# Sensor_Python.net
KiCad netlist of a schematic drawn in EAGLE
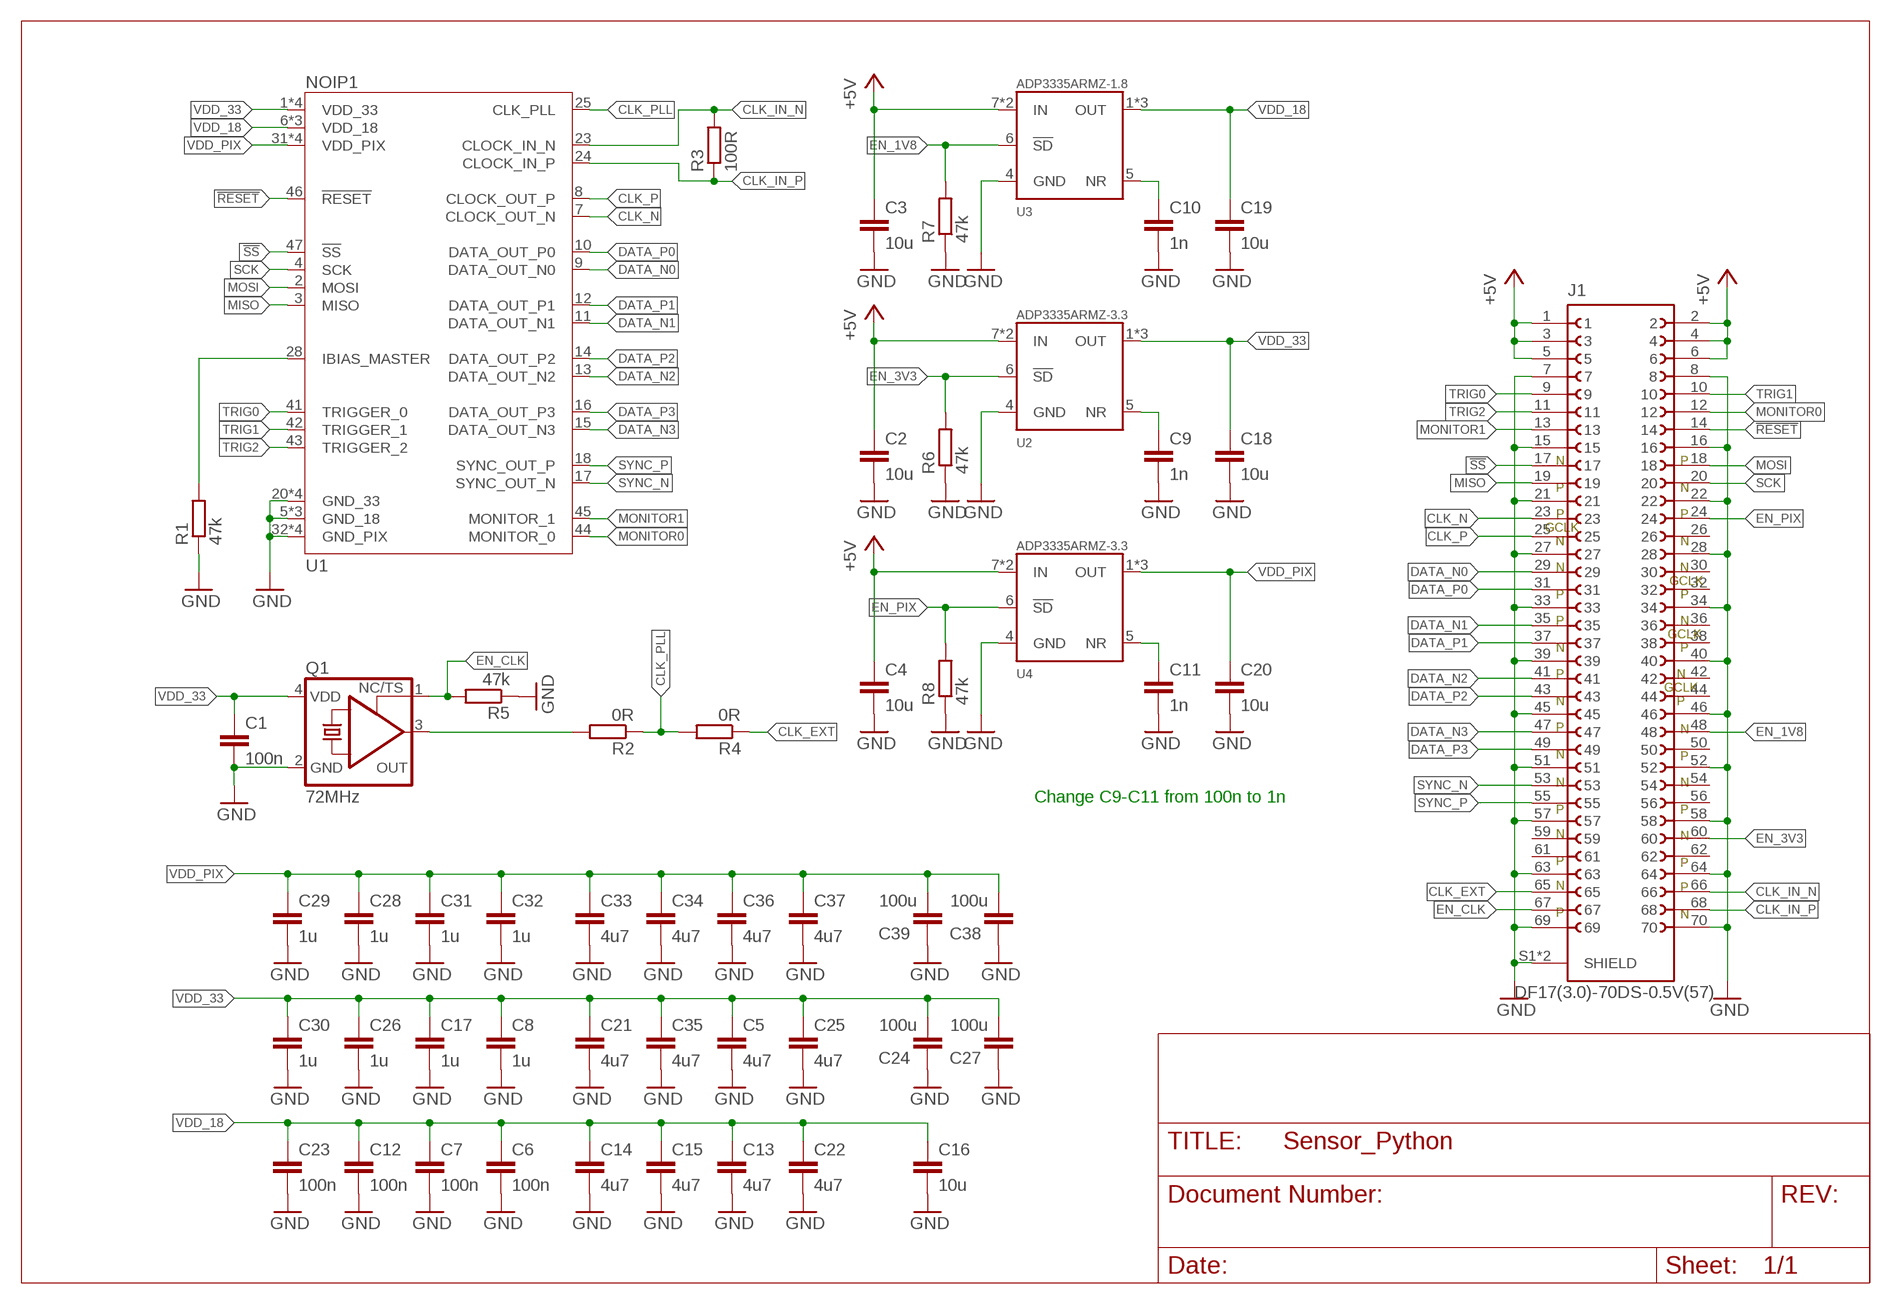
[diagram p0: schematic, sheet 1]

(export (version "E")
  (design (tool "Eeschema 10.0.6"))
  (components
    (comp (ref "C1")
      (value "100n")
      (footprint "eagle-import:C0402")
      (libsource (lib "eagle-import") (part "C-EUC0402"))
    )
    (comp (ref "C2")
      (value "10u")
      (footprint "eagle-import:C0603")
      (libsource (lib "eagle-import") (part "rcl_334_C-EUC0603"))
    )
    (comp (ref "C3")
      (value "10u")
      (footprint "eagle-import:C0603")
      (libsource (lib "eagle-import") (part "rcl_334_C-EUC0603"))
    )
    (comp (ref "C4")
      (value "10u")
      (footprint "eagle-import:C0603")
      (libsource (lib "eagle-import") (part "rcl_334_C-EUC0603"))
    )
    (comp (ref "C5")
      (value "4u7")
      (footprint "eagle-import:C0603")
      (libsource (lib "eagle-import") (part "rcl_334_C-EUC0603"))
    )
    (comp (ref "C6")
      (value "100n")
      (footprint "eagle-import:C0402")
      (libsource (lib "eagle-import") (part "rcl_334_C-EUC0402"))
    )
    (comp (ref "C7")
      (value "100n")
      (footprint "eagle-import:C0402")
      (libsource (lib "eagle-import") (part "rcl_334_C-EUC0402"))
    )
    (comp (ref "C8")
      (value "1u")
      (footprint "eagle-import:C0402")
      (libsource (lib "eagle-import") (part "rcl_334_C-EUC0402"))
    )
    (comp (ref "C9")
      (value "1n")
      (footprint "eagle-import:C0402")
      (libsource (lib "eagle-import") (part "rcl_334_C-EUC0402"))
    )
    (comp (ref "C10")
      (value "1n")
      (footprint "eagle-import:C0402")
      (libsource (lib "eagle-import") (part "rcl_334_C-EUC0402"))
    )
    (comp (ref "C11")
      (value "1n")
      (footprint "eagle-import:C0402")
      (libsource (lib "eagle-import") (part "rcl_334_C-EUC0402"))
    )
    (comp (ref "C12")
      (value "100n")
      (footprint "eagle-import:C0402")
      (libsource (lib "eagle-import") (part "rcl_334_C-EUC0402"))
    )
    (comp (ref "C13")
      (value "4u7")
      (footprint "eagle-import:C0603")
      (libsource (lib "eagle-import") (part "rcl_334_C-EUC0603"))
    )
    (comp (ref "C14")
      (value "4u7")
      (footprint "eagle-import:C0603")
      (libsource (lib "eagle-import") (part "rcl_334_C-EUC0603"))
    )
    (comp (ref "C15")
      (value "4u7")
      (footprint "eagle-import:C0603")
      (libsource (lib "eagle-import") (part "rcl_334_C-EUC0603"))
    )
    (comp (ref "C16")
      (value "10u")
      (footprint "eagle-import:C0603")
      (libsource (lib "eagle-import") (part "rcl_334_C-EUC0603"))
    )
    (comp (ref "C17")
      (value "1u")
      (footprint "eagle-import:C0402")
      (libsource (lib "eagle-import") (part "rcl_334_C-EUC0402"))
    )
    (comp (ref "C18")
      (value "10u")
      (footprint "eagle-import:C0603")
      (libsource (lib "eagle-import") (part "rcl_334_C-EUC0603"))
    )
    (comp (ref "C19")
      (value "10u")
      (footprint "eagle-import:C0603")
      (libsource (lib "eagle-import") (part "rcl_334_C-EUC0603"))
    )
    (comp (ref "C20")
      (value "10u")
      (footprint "eagle-import:C0603")
      (libsource (lib "eagle-import") (part "rcl_334_C-EUC0603"))
    )
    (comp (ref "C21")
      (value "4u7")
      (footprint "eagle-import:C0603")
      (libsource (lib "eagle-import") (part "rcl_334_C-EUC0603"))
    )
    (comp (ref "C22")
      (value "4u7")
      (footprint "eagle-import:C0603")
      (libsource (lib "eagle-import") (part "rcl_334_C-EUC0603"))
    )
    (comp (ref "C23")
      (value "100n")
      (footprint "eagle-import:C0402")
      (libsource (lib "eagle-import") (part "rcl_334_C-EUC0402"))
    )
    (comp (ref "C24")
      (value "100u")
      (footprint "eagle-import:C1206")
      (libsource (lib "eagle-import") (part "rcl_334_C-EUC1206"))
    )
    (comp (ref "C25")
      (value "4u7")
      (footprint "eagle-import:C0603")
      (libsource (lib "eagle-import") (part "rcl_334_C-EUC0603"))
    )
    (comp (ref "C26")
      (value "1u")
      (footprint "eagle-import:C0402")
      (libsource (lib "eagle-import") (part "rcl_334_C-EUC0402"))
    )
    (comp (ref "C27")
      (value "100u")
      (footprint "eagle-import:C1206")
      (libsource (lib "eagle-import") (part "rcl_334_C-EUC1206"))
    )
    (comp (ref "C28")
      (value "1u")
      (footprint "eagle-import:C0402")
      (libsource (lib "eagle-import") (part "rcl_334_C-EUC0402"))
    )
    (comp (ref "C29")
      (value "1u")
      (footprint "eagle-import:C0402")
      (libsource (lib "eagle-import") (part "rcl_334_C-EUC0402"))
    )
    (comp (ref "C30")
      (value "1u")
      (footprint "eagle-import:C0402")
      (libsource (lib "eagle-import") (part "rcl_334_C-EUC0402"))
    )
    (comp (ref "C31")
      (value "1u")
      (footprint "eagle-import:C0402")
      (libsource (lib "eagle-import") (part "rcl_334_C-EUC0402"))
    )
    (comp (ref "C32")
      (value "1u")
      (footprint "eagle-import:C0402")
      (libsource (lib "eagle-import") (part "rcl_334_C-EUC0402"))
    )
    (comp (ref "C33")
      (value "4u7")
      (footprint "eagle-import:C0603")
      (libsource (lib "eagle-import") (part "rcl_334_C-EUC0603"))
    )
    (comp (ref "C34")
      (value "4u7")
      (footprint "eagle-import:C0603")
      (libsource (lib "eagle-import") (part "rcl_334_C-EUC0603"))
    )
    (comp (ref "C35")
      (value "4u7")
      (footprint "eagle-import:C0603")
      (libsource (lib "eagle-import") (part "rcl_334_C-EUC0603"))
    )
    (comp (ref "C36")
      (value "4u7")
      (footprint "eagle-import:C0603")
      (libsource (lib "eagle-import") (part "rcl_334_C-EUC0603"))
    )
    (comp (ref "C37")
      (value "4u7")
      (footprint "eagle-import:C0603")
      (libsource (lib "eagle-import") (part "rcl_334_C-EUC0603"))
    )
    (comp (ref "C38")
      (value "100u")
      (footprint "eagle-import:C1206")
      (libsource (lib "eagle-import") (part "rcl_334_C-EUC1206"))
    )
    (comp (ref "C39")
      (value "100u")
      (footprint "eagle-import:C1206")
      (libsource (lib "eagle-import") (part "rcl_334_C-EUC1206"))
    )
    (comp (ref "J1")
      (value "DF17(3.0)-70DS-0.5V(57)")
      (footprint "eagle-import:DF17(3.0)-70DS-0.5V(57)")
      (libsource (lib "eagle-import") (part "DF17(3.0)-70DS-0.5V(57)"))
    )
    (comp (ref "Q1")
      (value "72MHz")
      (footprint "eagle-import:3.2X2.5_KXO-V96")
      (libsource (lib "eagle-import") (part "KXO-PXO/XO-V96"))
    )
    (comp (ref "R1")
      (value "47k")
      (footprint "eagle-import:R0402")
      (libsource (lib "eagle-import") (part "R-EU_R0402"))
    )
    (comp (ref "R2")
      (value "0R")
      (footprint "eagle-import:R0402")
      (libsource (lib "eagle-import") (part "R-EU_R0402"))
    )
    (comp (ref "R3")
      (value "100R")
      (footprint "eagle-import:R0402")
      (libsource (lib "eagle-import") (part "R-EU_R0402"))
    )
    (comp (ref "R4")
      (value "0R")
      (footprint "eagle-import:R0402")
      (libsource (lib "eagle-import") (part "R-EU_R0402"))
    )
    (comp (ref "R5")
      (value "47k")
      (footprint "eagle-import:R0402")
      (libsource (lib "eagle-import") (part "R-EU_R0402"))
    )
    (comp (ref "R6")
      (value "47k")
      (footprint "eagle-import:R0402")
      (libsource (lib "eagle-import") (part "R-EU_R0402"))
    )
    (comp (ref "R7")
      (value "47k")
      (footprint "eagle-import:R0402")
      (libsource (lib "eagle-import") (part "R-EU_R0402"))
    )
    (comp (ref "R8")
      (value "47k")
      (footprint "eagle-import:R0402")
      (libsource (lib "eagle-import") (part "R-EU_R0402"))
    )
    (comp (ref "U1")
      (value "NOIP1")
      (footprint "eagle-import:LCC-44")
      (libsource (lib "eagle-import") (part "NOIP1"))
    )
    (comp (ref "U2")
      (value "ADP3335ARMZ-3.3")
      (footprint "eagle-import:MSOP08")
      (libsource (lib "eagle-import") (part "ADP3335ARMZ"))
    )
    (comp (ref "U3")
      (value "ADP3335ARMZ-1.8")
      (footprint "eagle-import:MSOP08")
      (libsource (lib "eagle-import") (part "ADP3335ARMZ"))
    )
    (comp (ref "U4")
      (value "ADP3335ARMZ-3.3")
      (footprint "eagle-import:MSOP08")
      (libsource (lib "eagle-import") (part "ADP3335ARMZ"))
    )
  )
  (nets
    (net (code "1") (name "+5V") (class "Default")
      (node (ref "C2") (pin "1") (pinfunction "1_1") (pintype "passive"))
      (node (ref "C3") (pin "1") (pinfunction "1_1") (pintype "passive"))
      (node (ref "C4") (pin "1") (pinfunction "1_1") (pintype "passive"))
      (node (ref "J1") (pin "1") (pinfunction "1_1") (pintype "passive"))
      (node (ref "J1") (pin "2") (pinfunction "2_2") (pintype "passive"))
      (node (ref "J1") (pin "3") (pinfunction "3_3") (pintype "passive"))
      (node (ref "J1") (pin "4") (pinfunction "4_4") (pintype "passive"))
      (node (ref "J1") (pin "5") (pinfunction "5_5") (pintype "passive"))
      (node (ref "J1") (pin "6") (pinfunction "6_6") (pintype "passive"))
      (node (ref "U2") (pin "7") (pinfunction "IN_7") (pintype "power_in"))
      (node (ref "U2") (pin "8") (pinfunction "IN_8") (pintype "power_in"))
      (node (ref "U3") (pin "7") (pinfunction "IN_7") (pintype "power_in"))
      (node (ref "U3") (pin "8") (pinfunction "IN_8") (pintype "power_in"))
      (node (ref "U4") (pin "7") (pinfunction "IN_7") (pintype "power_in"))
      (node (ref "U4") (pin "8") (pinfunction "IN_8") (pintype "power_in"))
    )
    (net (code "2") (name "/~{RESET}") (class "Default")
      (node (ref "J1") (pin "14") (pinfunction "14_14") (pintype "passive"))
      (node (ref "U1") (pin "46") (pinfunction "~{RESET}_46") (pintype "input"))
    )
    (net (code "3") (name "/~{SS}") (class "Default")
      (node (ref "J1") (pin "17") (pinfunction "17_17") (pintype "passive"))
      (node (ref "U1") (pin "47") (pinfunction "~{SS}_47") (pintype "input"))
    )
    (net (code "4") (name "CLK_EXT") (class "Default")
      (node (ref "J1") (pin "65") (pinfunction "65_65") (pintype "passive"))
      (node (ref "R4") (pin "1") (pinfunction "1_1") (pintype "passive"))
    )
    (net (code "5") (name "CLK_IN_N") (class "Default")
      (node (ref "J1") (pin "66") (pinfunction "66_66") (pintype "passive"))
      (node (ref "R3") (pin "2") (pinfunction "2_2") (pintype "passive"))
      (node (ref "U1") (pin "23") (pinfunction "CLOCK_IN_N_23") (pintype "input"))
    )
    (net (code "6") (name "CLK_IN_P") (class "Default")
      (node (ref "J1") (pin "68") (pinfunction "68_68") (pintype "passive"))
      (node (ref "R3") (pin "1") (pinfunction "1_1") (pintype "passive"))
      (node (ref "U1") (pin "24") (pinfunction "CLOCK_IN_P_24") (pintype "input"))
    )
    (net (code "7") (name "CLK_N") (class "Default")
      (node (ref "J1") (pin "23") (pinfunction "23_23") (pintype "passive"))
      (node (ref "U1") (pin "7") (pinfunction "CLOCK_OUT_N_7") (pintype "output"))
    )
    (net (code "8") (name "CLK_P") (class "Default")
      (node (ref "J1") (pin "25") (pinfunction "25_25") (pintype "passive"))
      (node (ref "U1") (pin "8") (pinfunction "CLOCK_OUT_P_8") (pintype "output"))
    )
    (net (code "9") (name "CLK_PLL") (class "Default")
      (node (ref "R2") (pin "1") (pinfunction "1_1") (pintype "passive"))
      (node (ref "R4") (pin "2") (pinfunction "2_2") (pintype "passive"))
      (node (ref "U1") (pin "25") (pinfunction "CLK_PLL_25") (pintype "input"))
    )
    (net (code "10") (name "DATA_N0") (class "Default")
      (node (ref "J1") (pin "29") (pinfunction "29_29") (pintype "passive"))
      (node (ref "U1") (pin "9") (pinfunction "DATA_OUT_N0_9") (pintype "output"))
    )
    (net (code "11") (name "DATA_N1") (class "Default")
      (node (ref "J1") (pin "35") (pinfunction "35_35") (pintype "passive"))
      (node (ref "U1") (pin "11") (pinfunction "DATA_OUT_N1_11") (pintype "output"))
    )
    (net (code "12") (name "DATA_N2") (class "Default")
      (node (ref "J1") (pin "41") (pinfunction "41_41") (pintype "passive"))
      (node (ref "U1") (pin "13") (pinfunction "DATA_OUT_N2_13") (pintype "output"))
    )
    (net (code "13") (name "DATA_N3") (class "Default")
      (node (ref "J1") (pin "47") (pinfunction "47_47") (pintype "passive"))
      (node (ref "U1") (pin "15") (pinfunction "DATA_OUT_N3_15") (pintype "output"))
    )
    (net (code "14") (name "DATA_P0") (class "Default")
      (node (ref "J1") (pin "31") (pinfunction "31_31") (pintype "passive"))
      (node (ref "U1") (pin "10") (pinfunction "DATA_OUT_P0_10") (pintype "output"))
    )
    (net (code "15") (name "DATA_P1") (class "Default")
      (node (ref "J1") (pin "37") (pinfunction "37_37") (pintype "passive"))
      (node (ref "U1") (pin "12") (pinfunction "DATA_OUT_P1_12") (pintype "output"))
    )
    (net (code "16") (name "DATA_P2") (class "Default")
      (node (ref "J1") (pin "43") (pinfunction "43_43") (pintype "passive"))
      (node (ref "U1") (pin "14") (pinfunction "DATA_OUT_P2_14") (pintype "output"))
    )
    (net (code "17") (name "DATA_P3") (class "Default")
      (node (ref "J1") (pin "49") (pinfunction "49_49") (pintype "passive"))
      (node (ref "U1") (pin "16") (pinfunction "DATA_OUT_P3_16") (pintype "output"))
    )
    (net (code "18") (name "EN_1V8") (class "Default")
      (node (ref "J1") (pin "48") (pinfunction "48_48") (pintype "passive"))
      (node (ref "R7") (pin "2") (pinfunction "2_2") (pintype "passive"))
      (node (ref "U3") (pin "6") (pinfunction "~{SD}_6") (pintype "power_in"))
    )
    (net (code "19") (name "EN_3V3") (class "Default")
      (node (ref "J1") (pin "60") (pinfunction "60_60") (pintype "passive"))
      (node (ref "R6") (pin "2") (pinfunction "2_2") (pintype "passive"))
      (node (ref "U2") (pin "6") (pinfunction "~{SD}_6") (pintype "power_in"))
    )
    (net (code "20") (name "EN_CLK") (class "Default")
      (node (ref "J1") (pin "67") (pinfunction "67_67") (pintype "passive"))
      (node (ref "Q1") (pin "1") (pinfunction "TS_1") (pintype "passive"))
      (node (ref "R5") (pin "2") (pinfunction "2_2") (pintype "passive"))
    )
    (net (code "21") (name "EN_PIX") (class "Default")
      (node (ref "J1") (pin "24") (pinfunction "24_24") (pintype "passive"))
      (node (ref "R8") (pin "2") (pinfunction "2_2") (pintype "passive"))
      (node (ref "U4") (pin "6") (pinfunction "~{SD}_6") (pintype "power_in"))
    )
    (net (code "22") (name "GND") (class "Default")
      (node (ref "C1") (pin "2") (pinfunction "2_2") (pintype "passive"))
      (node (ref "C10") (pin "2") (pinfunction "2_2") (pintype "passive"))
      (node (ref "C11") (pin "2") (pinfunction "2_2") (pintype "passive"))
      (node (ref "C12") (pin "2") (pinfunction "2_2") (pintype "passive"))
      (node (ref "C13") (pin "2") (pinfunction "2_2") (pintype "passive"))
      (node (ref "C14") (pin "2") (pinfunction "2_2") (pintype "passive"))
      (node (ref "C15") (pin "2") (pinfunction "2_2") (pintype "passive"))
      (node (ref "C16") (pin "2") (pinfunction "2_2") (pintype "passive"))
      (node (ref "C17") (pin "2") (pinfunction "2_2") (pintype "passive"))
      (node (ref "C18") (pin "2") (pinfunction "2_2") (pintype "passive"))
      (node (ref "C19") (pin "2") (pinfunction "2_2") (pintype "passive"))
      (node (ref "C2") (pin "2") (pinfunction "2_2") (pintype "passive"))
      (node (ref "C20") (pin "2") (pinfunction "2_2") (pintype "passive"))
      (node (ref "C21") (pin "2") (pinfunction "2_2") (pintype "passive"))
      (node (ref "C22") (pin "2") (pinfunction "2_2") (pintype "passive"))
      (node (ref "C23") (pin "2") (pinfunction "2_2") (pintype "passive"))
      (node (ref "C24") (pin "2") (pinfunction "2_2") (pintype "passive"))
      (node (ref "C25") (pin "2") (pinfunction "2_2") (pintype "passive"))
      (node (ref "C26") (pin "2") (pinfunction "2_2") (pintype "passive"))
      (node (ref "C27") (pin "2") (pinfunction "2_2") (pintype "passive"))
      (node (ref "C28") (pin "2") (pinfunction "2_2") (pintype "passive"))
      (node (ref "C29") (pin "2") (pinfunction "2_2") (pintype "passive"))
      (node (ref "C3") (pin "2") (pinfunction "2_2") (pintype "passive"))
      (node (ref "C30") (pin "2") (pinfunction "2_2") (pintype "passive"))
      (node (ref "C31") (pin "2") (pinfunction "2_2") (pintype "passive"))
      (node (ref "C32") (pin "2") (pinfunction "2_2") (pintype "passive"))
      (node (ref "C33") (pin "2") (pinfunction "2_2") (pintype "passive"))
      (node (ref "C34") (pin "2") (pinfunction "2_2") (pintype "passive"))
      (node (ref "C35") (pin "2") (pinfunction "2_2") (pintype "passive"))
      (node (ref "C36") (pin "2") (pinfunction "2_2") (pintype "passive"))
      (node (ref "C37") (pin "2") (pinfunction "2_2") (pintype "passive"))
      (node (ref "C38") (pin "2") (pinfunction "2_2") (pintype "passive"))
      (node (ref "C39") (pin "2") (pinfunction "2_2") (pintype "passive"))
      (node (ref "C4") (pin "2") (pinfunction "2_2") (pintype "passive"))
      (node (ref "C5") (pin "2") (pinfunction "2_2") (pintype "passive"))
      (node (ref "C6") (pin "2") (pinfunction "2_2") (pintype "passive"))
      (node (ref "C7") (pin "2") (pinfunction "2_2") (pintype "passive"))
      (node (ref "C8") (pin "2") (pinfunction "2_2") (pintype "passive"))
      (node (ref "C9") (pin "2") (pinfunction "2_2") (pintype "passive"))
      (node (ref "J1") (pin "15") (pinfunction "15_15") (pintype "passive"))
      (node (ref "J1") (pin "16") (pinfunction "16_16") (pintype "passive"))
      (node (ref "J1") (pin "21") (pinfunction "21_21") (pintype "passive"))
      (node (ref "J1") (pin "22") (pinfunction "22_22") (pintype "passive"))
      (node (ref "J1") (pin "27") (pinfunction "27_27") (pintype "passive"))
      (node (ref "J1") (pin "28") (pinfunction "28_28") (pintype "passive"))
      (node (ref "J1") (pin "33") (pinfunction "33_33") (pintype "passive"))
      (node (ref "J1") (pin "34") (pinfunction "34_34") (pintype "passive"))
      (node (ref "J1") (pin "39") (pinfunction "39_39") (pintype "passive"))
      (node (ref "J1") (pin "40") (pinfunction "40_40") (pintype "passive"))
      (node (ref "J1") (pin "45") (pinfunction "45_45") (pintype "passive"))
      (node (ref "J1") (pin "46") (pinfunction "46_46") (pintype "passive"))
      (node (ref "J1") (pin "51") (pinfunction "51_51") (pintype "passive"))
      (node (ref "J1") (pin "52") (pinfunction "52_52") (pintype "passive"))
      (node (ref "J1") (pin "57") (pinfunction "57_57") (pintype "passive"))
      (node (ref "J1") (pin "58") (pinfunction "58_58") (pintype "passive"))
      (node (ref "J1") (pin "63") (pinfunction "63_63") (pintype "passive"))
      (node (ref "J1") (pin "64") (pinfunction "64_64") (pintype "passive"))
      (node (ref "J1") (pin "69") (pinfunction "69_69") (pintype "passive"))
      (node (ref "J1") (pin "7") (pinfunction "7_7") (pintype "passive"))
      (node (ref "J1") (pin "70") (pinfunction "70_70") (pintype "passive"))
      (node (ref "J1") (pin "8") (pinfunction "8_8") (pintype "passive"))
      (node (ref "J1") (pin "S1") (pinfunction "SHIELD_S1") (pintype "passive"))
      (node (ref "J1") (pin "S2") (pinfunction "SHIELD_S2") (pintype "passive"))
      (node (ref "Q1") (pin "2") (pinfunction "GND_2") (pintype "power_in"))
      (node (ref "R1") (pin "1") (pinfunction "1_1") (pintype "passive"))
      (node (ref "R5") (pin "1") (pinfunction "1_1") (pintype "passive"))
      (node (ref "R6") (pin "1") (pinfunction "1_1") (pintype "passive"))
      (node (ref "R7") (pin "1") (pinfunction "1_1") (pintype "passive"))
      (node (ref "R8") (pin "1") (pinfunction "1_1") (pintype "passive"))
      (node (ref "U1") (pin "20") (pinfunction "GND_33_20") (pintype "power_in"))
      (node (ref "U1") (pin "21") (pinfunction "GND_18_21") (pintype "power_in"))
      (node (ref "U1") (pin "27") (pinfunction "GND_18_27") (pintype "power_in"))
      (node (ref "U1") (pin "30") (pinfunction "GND_33_30") (pintype "power_in"))
      (node (ref "U1") (pin "32") (pinfunction "GND_PIX_32") (pintype "power_in"))
      (node (ref "U1") (pin "34") (pinfunction "GND_PIX_34") (pintype "power_in"))
      (node (ref "U1") (pin "35") (pinfunction "GND_33_35") (pintype "power_in"))
      (node (ref "U1") (pin "37") (pinfunction "GND_PIX_37") (pintype "power_in"))
      (node (ref "U1") (pin "39") (pinfunction "GND_PIX_39") (pintype "power_in"))
      (node (ref "U1") (pin "48") (pinfunction "GND_33_48") (pintype "power_in"))
      (node (ref "U1") (pin "5") (pinfunction "GND_18_5") (pintype "power_in"))
      (node (ref "U2") (pin "4") (pinfunction "GND_4") (pintype "power_in"))
      (node (ref "U3") (pin "4") (pinfunction "GND_4") (pintype "power_in"))
      (node (ref "U4") (pin "4") (pinfunction "GND_4") (pintype "power_in"))
    )
    (net (code "23") (name "MISO") (class "Default")
      (node (ref "J1") (pin "19") (pinfunction "19_19") (pintype "passive"))
      (node (ref "U1") (pin "3") (pinfunction "MISO_3") (pintype "output"))
    )
    (net (code "24") (name "MONITOR0") (class "Default")
      (node (ref "J1") (pin "12") (pinfunction "12_12") (pintype "passive"))
      (node (ref "U1") (pin "44") (pinfunction "MONITOR_0_44") (pintype "output"))
    )
    (net (code "25") (name "MONITOR1") (class "Default")
      (node (ref "J1") (pin "13") (pinfunction "13_13") (pintype "passive"))
      (node (ref "U1") (pin "45") (pinfunction "MONITOR_1_45") (pintype "output"))
    )
    (net (code "26") (name "MOSI") (class "Default")
      (node (ref "J1") (pin "18") (pinfunction "18_18") (pintype "passive"))
      (node (ref "U1") (pin "2") (pinfunction "MOSI_2") (pintype "input"))
    )
    (net (code "27") (name "Net-(Q1-OUT)") (class "Default")
      (node (ref "Q1") (pin "3") (pinfunction "OUT_3") (pintype "output"))
      (node (ref "R2") (pin "2") (pinfunction "2_2") (pintype "passive"))
    )
    (net (code "28") (name "Net-(U1-IBIAS_MASTER)") (class "Default")
      (node (ref "R1") (pin "2") (pinfunction "2_2") (pintype "passive"))
      (node (ref "U1") (pin "28") (pinfunction "IBIAS_MASTER_28") (pintype "passive"))
    )
    (net (code "29") (name "Net-(U2-NR)") (class "Default")
      (node (ref "C9") (pin "1") (pinfunction "1_1") (pintype "passive"))
      (node (ref "U2") (pin "5") (pinfunction "NR_5") (pintype "power_in"))
    )
    (net (code "30") (name "Net-(U3-NR)") (class "Default")
      (node (ref "C10") (pin "1") (pinfunction "1_1") (pintype "passive"))
      (node (ref "U3") (pin "5") (pinfunction "NR_5") (pintype "power_in"))
    )
    (net (code "31") (name "Net-(U4-NR)") (class "Default")
      (node (ref "C11") (pin "1") (pinfunction "1_1") (pintype "passive"))
      (node (ref "U4") (pin "5") (pinfunction "NR_5") (pintype "power_in"))
    )
    (net (code "32") (name "SCK") (class "Default")
      (node (ref "J1") (pin "20") (pinfunction "20_20") (pintype "passive"))
      (node (ref "U1") (pin "4") (pinfunction "SCK_4") (pintype "input"))
    )
    (net (code "33") (name "SYNC_N") (class "Default")
      (node (ref "J1") (pin "53") (pinfunction "53_53") (pintype "passive"))
      (node (ref "U1") (pin "17") (pinfunction "SYNC_OUT_N_17") (pintype "output"))
    )
    (net (code "34") (name "SYNC_P") (class "Default")
      (node (ref "J1") (pin "55") (pinfunction "55_55") (pintype "passive"))
      (node (ref "U1") (pin "18") (pinfunction "SYNC_OUT_P_18") (pintype "output"))
    )
    (net (code "35") (name "TRIG0") (class "Default")
      (node (ref "J1") (pin "9") (pinfunction "9_9") (pintype "passive"))
      (node (ref "U1") (pin "41") (pinfunction "TRIGGER_0_41") (pintype "input"))
    )
    (net (code "36") (name "TRIG1") (class "Default")
      (node (ref "J1") (pin "10") (pinfunction "10_10") (pintype "passive"))
      (node (ref "U1") (pin "42") (pinfunction "TRIGGER_1_42") (pintype "input"))
    )
    (net (code "37") (name "TRIG2") (class "Default")
      (node (ref "J1") (pin "11") (pinfunction "11_11") (pintype "passive"))
      (node (ref "U1") (pin "43") (pinfunction "TRIGGER_2_43") (pintype "input"))
    )
    (net (code "38") (name "VDD_18") (class "Default")
      (node (ref "C12") (pin "1") (pinfunction "1_1") (pintype "passive"))
      (node (ref "C13") (pin "1") (pinfunction "1_1") (pintype "passive"))
      (node (ref "C14") (pin "1") (pinfunction "1_1") (pintype "passive"))
      (node (ref "C15") (pin "1") (pinfunction "1_1") (pintype "passive"))
      (node (ref "C16") (pin "1") (pinfunction "1_1") (pintype "passive"))
      (node (ref "C19") (pin "1") (pinfunction "1_1") (pintype "passive"))
      (node (ref "C22") (pin "1") (pinfunction "1_1") (pintype "passive"))
      (node (ref "C23") (pin "1") (pinfunction "1_1") (pintype "passive"))
      (node (ref "C6") (pin "1") (pinfunction "1_1") (pintype "passive"))
      (node (ref "C7") (pin "1") (pinfunction "1_1") (pintype "passive"))
      (node (ref "U1") (pin "22") (pinfunction "VDD_18_22") (pintype "power_in"))
      (node (ref "U1") (pin "26") (pinfunction "VDD_18_26") (pintype "power_in"))
      (node (ref "U1") (pin "6") (pinfunction "VDD_18_6") (pintype "power_in"))
      (node (ref "U3") (pin "1") (pinfunction "OUT_1") (pintype "power_in"))
      (node (ref "U3") (pin "2") (pinfunction "OUT_2") (pintype "power_in"))
      (node (ref "U3") (pin "3") (pinfunction "OUT_3") (pintype "power_in"))
    )
    (net (code "39") (name "VDD_33") (class "Default")
      (node (ref "C1") (pin "1") (pinfunction "1_1") (pintype "passive"))
      (node (ref "C17") (pin "1") (pinfunction "1_1") (pintype "passive"))
      (node (ref "C18") (pin "1") (pinfunction "1_1") (pintype "passive"))
      (node (ref "C21") (pin "1") (pinfunction "1_1") (pintype "passive"))
      (node (ref "C24") (pin "1") (pinfunction "1_1") (pintype "passive"))
      (node (ref "C25") (pin "1") (pinfunction "1_1") (pintype "passive"))
      (node (ref "C26") (pin "1") (pinfunction "1_1") (pintype "passive"))
      (node (ref "C27") (pin "1") (pinfunction "1_1") (pintype "passive"))
      (node (ref "C30") (pin "1") (pinfunction "1_1") (pintype "passive"))
      (node (ref "C35") (pin "1") (pinfunction "1_1") (pintype "passive"))
      (node (ref "C5") (pin "1") (pinfunction "1_1") (pintype "passive"))
      (node (ref "C8") (pin "1") (pinfunction "1_1") (pintype "passive"))
      (node (ref "Q1") (pin "4") (pinfunction "VDD_4") (pintype "power_in"))
      (node (ref "U1") (pin "1") (pinfunction "VDD_33_1") (pintype "power_in"))
      (node (ref "U1") (pin "19") (pinfunction "VDD_33_19") (pintype "power_in"))
      (node (ref "U1") (pin "29") (pinfunction "VDD_33_29") (pintype "power_in"))
      (node (ref "U1") (pin "36") (pinfunction "VDD_33_36") (pintype "power_in"))
      (node (ref "U2") (pin "1") (pinfunction "OUT_1") (pintype "power_in"))
      (node (ref "U2") (pin "2") (pinfunction "OUT_2") (pintype "power_in"))
      (node (ref "U2") (pin "3") (pinfunction "OUT_3") (pintype "power_in"))
    )
    (net (code "40") (name "VDD_PIX") (class "Default")
      (node (ref "C20") (pin "1") (pinfunction "1_1") (pintype "passive"))
      (node (ref "C28") (pin "1") (pinfunction "1_1") (pintype "passive"))
      (node (ref "C29") (pin "1") (pinfunction "1_1") (pintype "passive"))
      (node (ref "C31") (pin "1") (pinfunction "1_1") (pintype "passive"))
      (node (ref "C32") (pin "1") (pinfunction "1_1") (pintype "passive"))
      (node (ref "C33") (pin "1") (pinfunction "1_1") (pintype "passive"))
      (node (ref "C34") (pin "1") (pinfunction "1_1") (pintype "passive"))
      (node (ref "C36") (pin "1") (pinfunction "1_1") (pintype "passive"))
      (node (ref "C37") (pin "1") (pinfunction "1_1") (pintype "passive"))
      (node (ref "C38") (pin "1") (pinfunction "1_1") (pintype "passive"))
      (node (ref "C39") (pin "1") (pinfunction "1_1") (pintype "passive"))
      (node (ref "U1") (pin "31") (pinfunction "VDD_PIX_31") (pintype "power_in"))
      (node (ref "U1") (pin "33") (pinfunction "VDD_PIX_33") (pintype "power_in"))
      (node (ref "U1") (pin "38") (pinfunction "VDD_PIX_38") (pintype "power_in"))
      (node (ref "U1") (pin "40") (pinfunction "VDD_PIX_40") (pintype "power_in"))
      (node (ref "U4") (pin "1") (pinfunction "OUT_1") (pintype "power_in"))
      (node (ref "U4") (pin "2") (pinfunction "OUT_2") (pintype "power_in"))
      (node (ref "U4") (pin "3") (pinfunction "OUT_3") (pintype "power_in"))
    )
    (net (code "41") (name "unconnected-(J1-Pad26)") (class "Default")
      (node (ref "J1") (pin "26") (pinfunction "26_26") (pintype "passive"))
    )
    (net (code "42") (name "unconnected-(J1-Pad30)") (class "Default")
      (node (ref "J1") (pin "30") (pinfunction "30_30") (pintype "passive"))
    )
    (net (code "43") (name "unconnected-(J1-Pad32)") (class "Default")
      (node (ref "J1") (pin "32") (pinfunction "32_32") (pintype "passive"))
    )
    (net (code "44") (name "unconnected-(J1-Pad36)") (class "Default")
      (node (ref "J1") (pin "36") (pinfunction "36_36") (pintype "passive"))
    )
    (net (code "45") (name "unconnected-(J1-Pad38)") (class "Default")
      (node (ref "J1") (pin "38") (pinfunction "38_38") (pintype "passive"))
    )
    (net (code "46") (name "unconnected-(J1-Pad42)") (class "Default")
      (node (ref "J1") (pin "42") (pinfunction "42_42") (pintype "passive"))
    )
    (net (code "47") (name "unconnected-(J1-Pad44)") (class "Default")
      (node (ref "J1") (pin "44") (pinfunction "44_44") (pintype "passive"))
    )
    (net (code "48") (name "unconnected-(J1-Pad50)") (class "Default")
      (node (ref "J1") (pin "50") (pinfunction "50_50") (pintype "passive"))
    )
    (net (code "49") (name "unconnected-(J1-Pad54)") (class "Default")
      (node (ref "J1") (pin "54") (pinfunction "54_54") (pintype "passive"))
    )
    (net (code "50") (name "unconnected-(J1-Pad56)") (class "Default")
      (node (ref "J1") (pin "56") (pinfunction "56_56") (pintype "passive"))
    )
    (net (code "51") (name "unconnected-(J1-Pad59)") (class "Default")
      (node (ref "J1") (pin "59") (pinfunction "59_59") (pintype "passive"))
    )
    (net (code "52") (name "unconnected-(J1-Pad61)") (class "Default")
      (node (ref "J1") (pin "61") (pinfunction "61_61") (pintype "passive"))
    )
    (net (code "53") (name "unconnected-(J1-Pad62)") (class "Default")
      (node (ref "J1") (pin "62") (pinfunction "62_62") (pintype "passive"))
    )
  )
)
